# LampenSteuerung_PWM.net
KiCad netlist of a schematic drawn in EAGLE
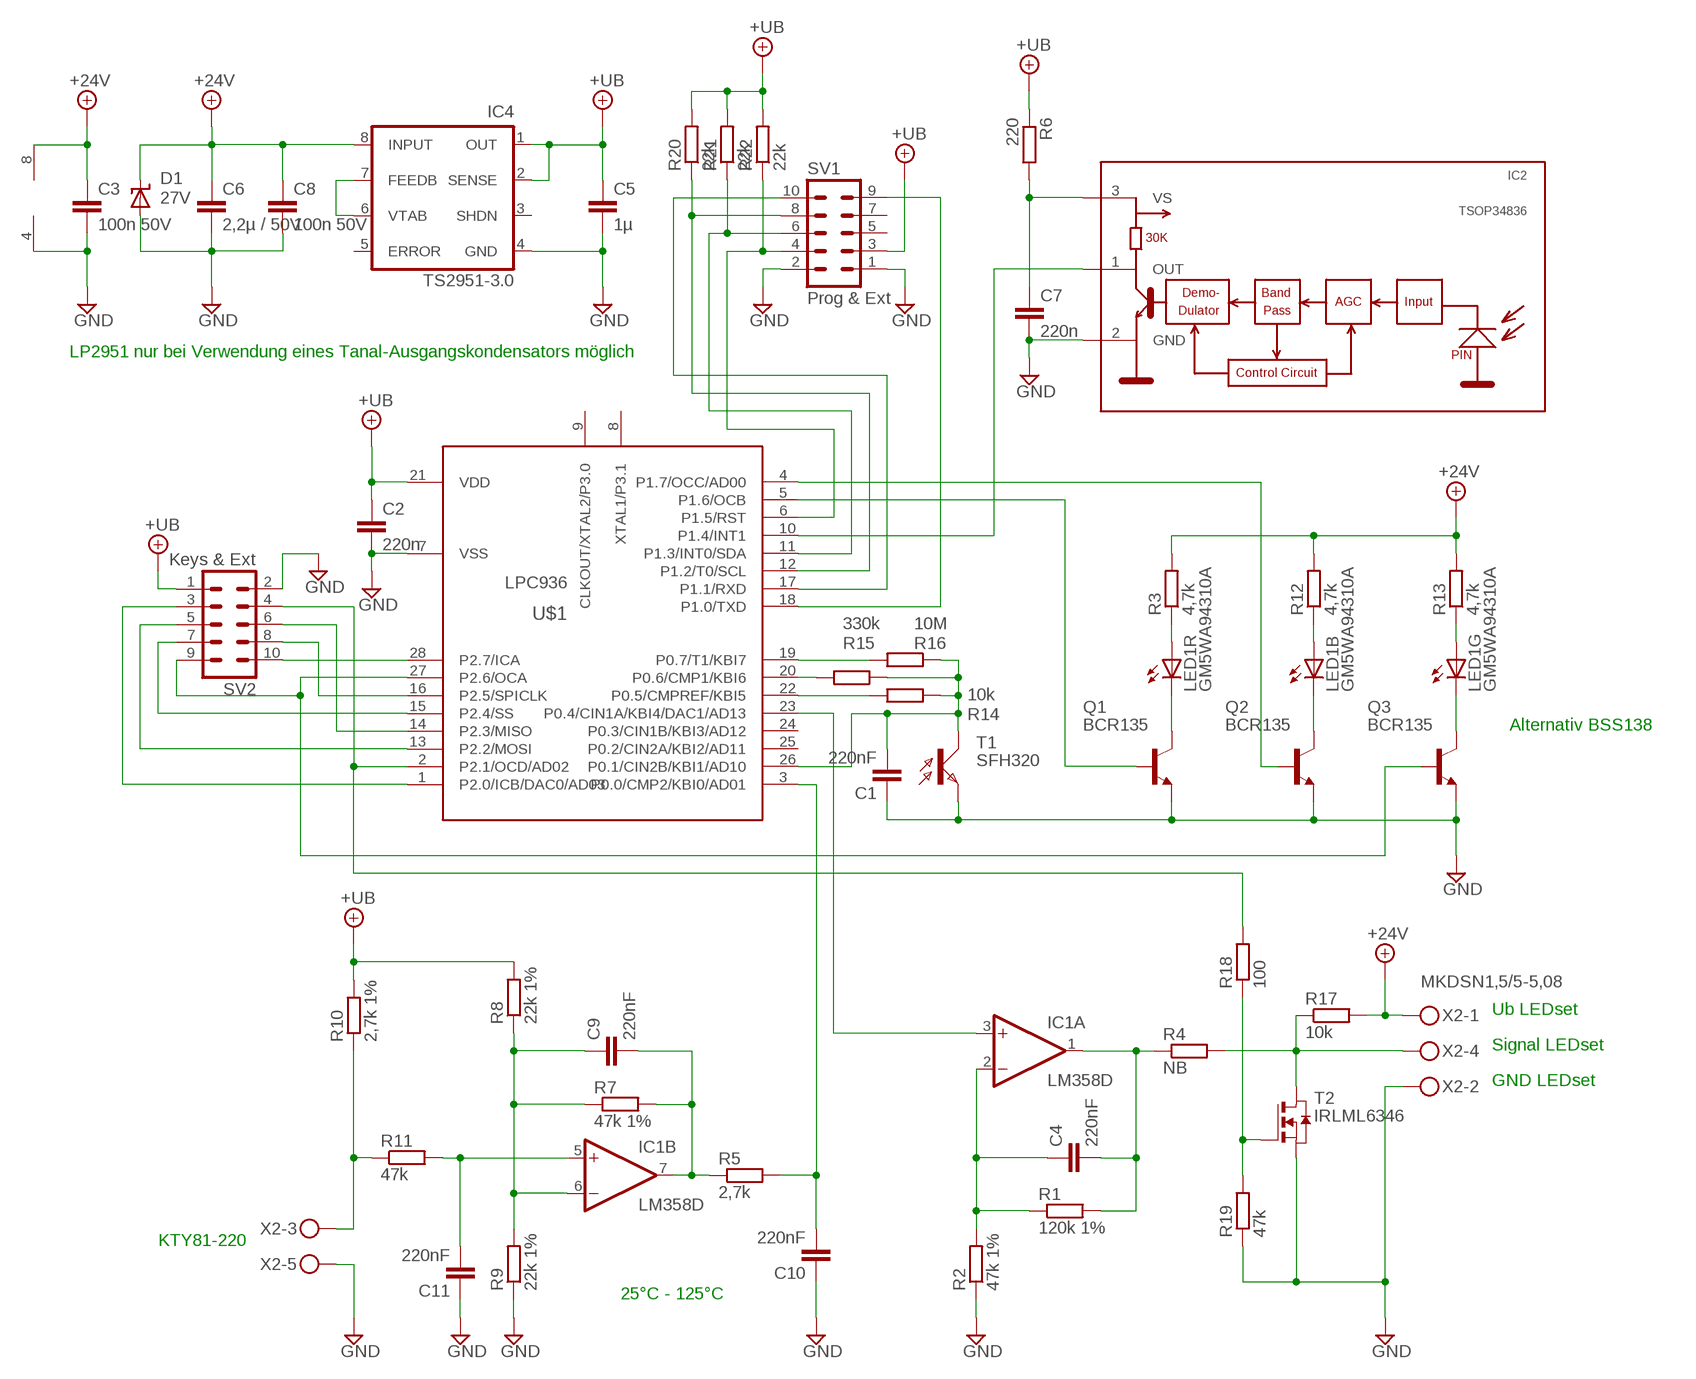
[diagram p0: schematic, sheet 1]

(export (version "E")
  (design (tool "Eeschema 10.0.6"))
  (components
    (comp (ref "C1")
      (value "220nF")
      (footprint "eagle-import:C0603")
      (libsource (lib "eagle-import") (part "C-EUC0603"))
    )
    (comp (ref "C2")
      (value "220n")
      (footprint "eagle-import:C0603")
      (libsource (lib "eagle-import") (part "C-EUC0603"))
    )
    (comp (ref "C3")
      (value "100n 50V")
      (footprint "eagle-import:C0603")
      (libsource (lib "eagle-import") (part "C-EUC0603"))
    )
    (comp (ref "C4")
      (value "220nF")
      (footprint "eagle-import:C0603")
      (libsource (lib "eagle-import") (part "C-EUC0603"))
    )
    (comp (ref "C5")
      (value "1µ")
      (footprint "eagle-import:C0805")
      (libsource (lib "eagle-import") (part "C-EUC0805"))
    )
    (comp (ref "C6")
      (value "2,2µ / 50V")
      (footprint "eagle-import:C1206")
      (libsource (lib "eagle-import") (part "C-EUC1206"))
    )
    (comp (ref "C7")
      (value "220n")
      (footprint "eagle-import:C0603")
      (libsource (lib "eagle-import") (part "C-EUC0603"))
    )
    (comp (ref "C8")
      (value "100n 50V")
      (footprint "eagle-import:C0603")
      (libsource (lib "eagle-import") (part "C-EUC0603"))
    )
    (comp (ref "C9")
      (value "220nF")
      (footprint "eagle-import:C0603")
      (libsource (lib "eagle-import") (part "C-EUC0603"))
    )
    (comp (ref "C10")
      (value "220nF")
      (footprint "eagle-import:C0603")
      (libsource (lib "eagle-import") (part "C-EUC0603"))
    )
    (comp (ref "C11")
      (value "220nF")
      (footprint "eagle-import:C0603")
      (libsource (lib "eagle-import") (part "C-EUC0603"))
    )
    (comp (ref "D1")
      (value "27V")
      (footprint "eagle-import:SMBJ")
      (libsource (lib "eagle-import") (part "SUPPRESSOR-SMBJ"))
    )
    (comp (ref "IC1")
      (value "LM358D")
      (footprint "eagle-import:SO08")
      (libsource (lib "eagle-import") (part "LM358D"))
    )
    (comp (ref "IC2")
      (value "TSOP34836")
      (footprint "eagle-import:TSOP348")
      (libsource (lib "eagle-import") (part "TSOP34836"))
    )
    (comp (ref "IC4")
      (value "TS2951-3.0")
      (footprint "eagle-import:SO-08")
      (libsource (lib "eagle-import") (part "LP2951?CM-3.0"))
    )
    (comp (ref "LED1")
      (value "GM5WA94310A")
      (footprint "eagle-import:GM5WA94310A")
      (libsource (lib "eagle-import") (part "GM5WA94310A"))
    )
    (comp (ref "Q1")
      (value "BCR135")
      (footprint "eagle-import:SOT23-BEC")
      (libsource (lib "eagle-import") (part "BCW60SMD"))
    )
    (comp (ref "Q2")
      (value "BCR135")
      (footprint "eagle-import:SOT23-BEC")
      (libsource (lib "eagle-import") (part "BCW60SMD"))
    )
    (comp (ref "Q3")
      (value "BCR135")
      (footprint "eagle-import:SOT23-BEC")
      (libsource (lib "eagle-import") (part "BCW60SMD"))
    )
    (comp (ref "R1")
      (value "120k 1%")
      (footprint "eagle-import:R0805")
      (libsource (lib "eagle-import") (part "R-EU_R0805"))
    )
    (comp (ref "R2")
      (value "47k 1%")
      (footprint "eagle-import:R0805")
      (libsource (lib "eagle-import") (part "R-EU_R0805"))
    )
    (comp (ref "R3")
      (value "4,7k")
      (footprint "eagle-import:R0805")
      (libsource (lib "eagle-import") (part "R-EU_R0805"))
    )
    (comp (ref "R4")
      (value "NB")
      (footprint "eagle-import:R0805")
      (libsource (lib "eagle-import") (part "R-EU_R0805"))
    )
    (comp (ref "R5")
      (value "2,7k")
      (footprint "eagle-import:R0805")
      (libsource (lib "eagle-import") (part "R-EU_R0805"))
    )
    (comp (ref "R6")
      (value "220")
      (footprint "eagle-import:R0805")
      (libsource (lib "eagle-import") (part "R-EU_R0805"))
    )
    (comp (ref "R7")
      (value "47k 1%")
      (footprint "eagle-import:R0805")
      (libsource (lib "eagle-import") (part "R-EU_R0805"))
    )
    (comp (ref "R8")
      (value "22k 1%")
      (footprint "eagle-import:R0805")
      (libsource (lib "eagle-import") (part "R-EU_R0805"))
    )
    (comp (ref "R9")
      (value "22k 1%")
      (footprint "eagle-import:R0805")
      (libsource (lib "eagle-import") (part "R-EU_R0805"))
    )
    (comp (ref "R10")
      (value "2,7k 1%")
      (footprint "eagle-import:R0805")
      (libsource (lib "eagle-import") (part "R-EU_R0805"))
    )
    (comp (ref "R11")
      (value "47k")
      (footprint "eagle-import:R0805")
      (libsource (lib "eagle-import") (part "R-EU_R0805"))
    )
    (comp (ref "R12")
      (value "4,7k")
      (footprint "eagle-import:R0805")
      (libsource (lib "eagle-import") (part "R-EU_R0805"))
    )
    (comp (ref "R13")
      (value "4,7k")
      (footprint "eagle-import:R0805")
      (libsource (lib "eagle-import") (part "R-EU_R0805"))
    )
    (comp (ref "R14")
      (value "10k")
      (footprint "eagle-import:R0805")
      (libsource (lib "eagle-import") (part "R-EU_R0805"))
    )
    (comp (ref "R15")
      (value "330k")
      (footprint "eagle-import:R0805")
      (libsource (lib "eagle-import") (part "R-EU_R0805"))
    )
    (comp (ref "R16")
      (value "10M")
      (footprint "eagle-import:R0805")
      (libsource (lib "eagle-import") (part "R-EU_R0805"))
    )
    (comp (ref "R17")
      (value "10k")
      (footprint "eagle-import:R0805")
      (libsource (lib "eagle-import") (part "R-EU_R0805"))
    )
    (comp (ref "R18")
      (value "100")
      (footprint "eagle-import:R0805")
      (libsource (lib "eagle-import") (part "R-EU_R0805"))
    )
    (comp (ref "R19")
      (value "47k")
      (footprint "eagle-import:R0805")
      (libsource (lib "eagle-import") (part "R-EU_R0805"))
    )
    (comp (ref "R20")
      (value "22k")
      (footprint "eagle-import:R0805")
      (libsource (lib "eagle-import") (part "R-EU_R0805"))
    )
    (comp (ref "R21")
      (value "22k")
      (footprint "eagle-import:R0805")
      (libsource (lib "eagle-import") (part "R-EU_R0805"))
    )
    (comp (ref "R22")
      (value "22k")
      (footprint "eagle-import:R0805")
      (libsource (lib "eagle-import") (part "R-EU_R0805"))
    )
    (comp (ref "SV1")
      (value "Prog & Ext")
      (footprint "eagle-import:MA05-2")
      (libsource (lib "eagle-import") (part "MA05-2"))
    )
    (comp (ref "SV2")
      (value "Keys & Ext")
      (footprint "eagle-import:MA05-2")
      (libsource (lib "eagle-import") (part "MA05-2"))
    )
    (comp (ref "T1")
      (value "SFH320")
      (footprint "eagle-import:PLCC2")
      (libsource (lib "eagle-import") (part "SFH320"))
    )
    (comp (ref "T2")
      (value "IRLML6346")
      (footprint "eagle-import:SOT-23")
      (libsource (lib "eagle-import") (part "NMOSSOT23"))
    )
    (comp (ref "U$1")
      (value "LPC936")
      (footprint "eagle-import:TSSOP28")
      (libsource (lib "eagle-import") (part "LPC936"))
    )
    (comp (ref "X2")
      (value "MKDSN1,5/5-5,08")
      (footprint "eagle-import:MKDSN1,5_5-5,08")
      (fields (field (name "MPN") "SMKDSN1,5/5-5,08"))
      (libsource (lib "eagle-import") (part "MKDSN1,5/5-5,08"))
    )
  )
  (nets
    (net (code "1") (name "+24V") (class "Default")
      (node (ref "C3") (pin "1") (pinfunction "1_1") (pintype "passive"))
      (node (ref "C6") (pin "1") (pinfunction "1_1") (pintype "passive"))
      (node (ref "C8") (pin "1") (pinfunction "1_1") (pintype "passive"))
      (node (ref "D1") (pin "C") (pinfunction "C_C") (pintype "passive"))
      (node (ref "IC1") (pin "8") (pinfunction "V+_8") (pintype "power_in"))
      (node (ref "IC4") (pin "8") (pinfunction "INPUT_8") (pintype "passive"))
      (node (ref "R12") (pin "2") (pinfunction "2_2") (pintype "passive"))
      (node (ref "R13") (pin "2") (pinfunction "2_2") (pintype "passive"))
      (node (ref "R17") (pin "2") (pinfunction "2_2") (pintype "passive"))
      (node (ref "R3") (pin "2") (pinfunction "2_2") (pintype "passive"))
      (node (ref "X2") (pin "1") (pinfunction "KL_1") (pintype "passive"))
    )
    (net (code "2") (name "+UB") (class "Default")
      (node (ref "C2") (pin "1") (pinfunction "1_1") (pintype "passive"))
      (node (ref "C5") (pin "1") (pinfunction "1_1") (pintype "passive"))
      (node (ref "IC4") (pin "1") (pinfunction "OUT_1") (pintype "output"))
      (node (ref "IC4") (pin "2") (pinfunction "SENSE_2") (pintype "input"))
      (node (ref "R10") (pin "2") (pinfunction "2_2") (pintype "passive"))
      (node (ref "R20") (pin "2") (pinfunction "2_2") (pintype "passive"))
      (node (ref "R21") (pin "2") (pinfunction "2_2") (pintype "passive"))
      (node (ref "R22") (pin "2") (pinfunction "2_2") (pintype "passive"))
      (node (ref "R6") (pin "1") (pinfunction "1_1") (pintype "passive"))
      (node (ref "R8") (pin "2") (pinfunction "2_2") (pintype "passive"))
      (node (ref "SV1") (pin "3") (pinfunction "3_3") (pintype "passive"))
      (node (ref "SV2") (pin "1") (pinfunction "1_1") (pintype "passive"))
      (node (ref "U$1") (pin "21") (pinfunction "VDD_21") (pintype "bidirectional"))
    )
    (net (code "3") (name "GND") (class "Default")
      (node (ref "C1") (pin "1") (pinfunction "1_1") (pintype "passive"))
      (node (ref "C10") (pin "1") (pinfunction "1_1") (pintype "passive"))
      (node (ref "C11") (pin "1") (pinfunction "1_1") (pintype "passive"))
      (node (ref "C2") (pin "2") (pinfunction "2_2") (pintype "passive"))
      (node (ref "C3") (pin "2") (pinfunction "2_2") (pintype "passive"))
      (node (ref "C5") (pin "2") (pinfunction "2_2") (pintype "passive"))
      (node (ref "C6") (pin "2") (pinfunction "2_2") (pintype "passive"))
      (node (ref "C7") (pin "2") (pinfunction "2_2") (pintype "passive"))
      (node (ref "C8") (pin "2") (pinfunction "2_2") (pintype "passive"))
      (node (ref "D1") (pin "A") (pinfunction "A_A") (pintype "passive"))
      (node (ref "IC1") (pin "4") (pinfunction "V-_4") (pintype "power_in"))
      (node (ref "IC2") (pin "2") (pinfunction "GND_2") (pintype "power_in"))
      (node (ref "IC4") (pin "4") (pinfunction "GND_4") (pintype "power_in"))
      (node (ref "Q1") (pin "E") (pinfunction "E_E") (pintype "passive"))
      (node (ref "Q2") (pin "E") (pinfunction "E_E") (pintype "passive"))
      (node (ref "Q3") (pin "E") (pinfunction "E_E") (pintype "passive"))
      (node (ref "R19") (pin "1") (pinfunction "1_1") (pintype "passive"))
      (node (ref "R2") (pin "1") (pinfunction "1_1") (pintype "passive"))
      (node (ref "R9") (pin "1") (pinfunction "1_1") (pintype "passive"))
      (node (ref "SV1") (pin "1") (pinfunction "1_1") (pintype "passive"))
      (node (ref "SV1") (pin "2") (pinfunction "2_2") (pintype "passive"))
      (node (ref "SV2") (pin "2") (pinfunction "2_2") (pintype "passive"))
      (node (ref "T1") (pin "C") (pinfunction "E_C") (pintype "passive"))
      (node (ref "T2") (pin "2") (pinfunction "S_2") (pintype "passive"))
      (node (ref "U$1") (pin "7") (pinfunction "VSS_7") (pintype "bidirectional"))
      (node (ref "X2") (pin "2") (pinfunction "KL_2") (pintype "passive"))
      (node (ref "X2") (pin "5") (pinfunction "KL_5") (pintype "passive"))
    )
    (net (code "4") (name "Net-(IC1A-+IN)") (class "Default")
      (node (ref "IC1") (pin "3") (pinfunction "+IN_3") (pintype "input"))
      (node (ref "U$1") (pin "23") (pinfunction "P0.4/CIN1A/KBI4/DAC1/AD13_23") (pintype "bidirectional"))
    )
    (net (code "5") (name "Net-(IC1A--IN)") (class "Default")
      (node (ref "C4") (pin "1") (pinfunction "1_1") (pintype "passive"))
      (node (ref "IC1") (pin "2") (pinfunction "-IN_2") (pintype "input"))
      (node (ref "R1") (pin "1") (pinfunction "1_1") (pintype "passive"))
      (node (ref "R2") (pin "2") (pinfunction "2_2") (pintype "passive"))
    )
    (net (code "6") (name "Net-(IC1A-OUT)") (class "Default")
      (node (ref "C4") (pin "2") (pinfunction "2_2") (pintype "passive"))
      (node (ref "IC1") (pin "1") (pinfunction "OUT_1") (pintype "output"))
      (node (ref "R1") (pin "2") (pinfunction "2_2") (pintype "passive"))
      (node (ref "R4") (pin "1") (pinfunction "1_1") (pintype "passive"))
    )
    (net (code "7") (name "Net-(IC1B-+IN)") (class "Default")
      (node (ref "C11") (pin "2") (pinfunction "2_2") (pintype "passive"))
      (node (ref "IC1") (pin "5") (pinfunction "+IN_5") (pintype "input"))
      (node (ref "R11") (pin "2") (pinfunction "2_2") (pintype "passive"))
    )
    (net (code "8") (name "Net-(IC1B--IN)") (class "Default")
      (node (ref "C9") (pin "1") (pinfunction "1_1") (pintype "passive"))
      (node (ref "IC1") (pin "6") (pinfunction "-IN_6") (pintype "input"))
      (node (ref "R7") (pin "1") (pinfunction "1_1") (pintype "passive"))
      (node (ref "R8") (pin "1") (pinfunction "1_1") (pintype "passive"))
      (node (ref "R9") (pin "2") (pinfunction "2_2") (pintype "passive"))
    )
    (net (code "9") (name "Net-(IC1B-OUT)") (class "Default")
      (node (ref "C9") (pin "2") (pinfunction "2_2") (pintype "passive"))
      (node (ref "IC1") (pin "7") (pinfunction "OUT_7") (pintype "output"))
      (node (ref "R5") (pin "1") (pinfunction "1_1") (pintype "passive"))
      (node (ref "R7") (pin "2") (pinfunction "2_2") (pintype "passive"))
    )
    (net (code "10") (name "Net-(IC2-OUT)") (class "Default")
      (node (ref "IC2") (pin "1") (pinfunction "OUT_1") (pintype "output"))
      (node (ref "U$1") (pin "10") (pinfunction "P1.4/INT1_10") (pintype "bidirectional"))
    )
    (net (code "11") (name "Net-(IC2-VS)") (class "Default")
      (node (ref "C7") (pin "1") (pinfunction "1_1") (pintype "passive"))
      (node (ref "IC2") (pin "3") (pinfunction "VS_3") (pintype "power_in"))
      (node (ref "R6") (pin "2") (pinfunction "2_2") (pintype "passive"))
    )
    (net (code "12") (name "Net-(IC4-FEEDB)") (class "Default")
      (node (ref "IC4") (pin "6") (pinfunction "VTAB_6") (pintype "input"))
      (node (ref "IC4") (pin "7") (pinfunction "FEEDB_7") (pintype "output"))
    )
    (net (code "13") (name "Net-(LED1A-A)") (class "Default")
      (node (ref "LED1") (pin "1") (pinfunction "A_1") (pintype "passive"))
      (node (ref "R12") (pin "1") (pinfunction "1_1") (pintype "passive"))
    )
    (net (code "14") (name "Net-(LED1A-C)") (class "Default")
      (node (ref "LED1") (pin "6") (pinfunction "C_6") (pintype "passive"))
      (node (ref "Q2") (pin "C") (pinfunction "C_C") (pintype "passive"))
    )
    (net (code "15") (name "Net-(LED1B-A)") (class "Default")
      (node (ref "LED1") (pin "3") (pinfunction "A_3") (pintype "passive"))
      (node (ref "R13") (pin "1") (pinfunction "1_1") (pintype "passive"))
    )
    (net (code "16") (name "Net-(LED1B-C)") (class "Default")
      (node (ref "LED1") (pin "4") (pinfunction "C_4") (pintype "passive"))
      (node (ref "Q3") (pin "C") (pinfunction "C_C") (pintype "passive"))
    )
    (net (code "17") (name "Net-(LED1C-A)") (class "Default")
      (node (ref "LED1") (pin "2") (pinfunction "A_2") (pintype "passive"))
      (node (ref "R3") (pin "1") (pinfunction "1_1") (pintype "passive"))
    )
    (net (code "18") (name "Net-(LED1C-C)") (class "Default")
      (node (ref "LED1") (pin "5") (pinfunction "C_5") (pintype "passive"))
      (node (ref "Q1") (pin "C") (pinfunction "C_C") (pintype "passive"))
    )
    (net (code "19") (name "Net-(T1-C)") (class "Default")
      (node (ref "C1") (pin "2") (pinfunction "2_2") (pintype "passive"))
      (node (ref "R14") (pin "1") (pinfunction "1_1") (pintype "passive"))
      (node (ref "R15") (pin "1") (pinfunction "1_1") (pintype "passive"))
      (node (ref "R16") (pin "1") (pinfunction "1_1") (pintype "passive"))
      (node (ref "T1") (pin "A") (pinfunction "C_A") (pintype "passive"))
      (node (ref "U$1") (pin "26") (pinfunction "P0.1/CIN2B/KBI1/AD10_26") (pintype "bidirectional"))
    )
    (net (code "20") (name "Net-(T2-D)") (class "Default")
      (node (ref "R17") (pin "1") (pinfunction "1_1") (pintype "passive"))
      (node (ref "R4") (pin "2") (pinfunction "2_2") (pintype "passive"))
      (node (ref "T2") (pin "1") (pinfunction "D_1") (pintype "passive"))
      (node (ref "X2") (pin "4") (pinfunction "KL_4") (pintype "passive"))
    )
    (net (code "21") (name "Net-(T2-G)") (class "Default")
      (node (ref "R18") (pin "1") (pinfunction "1_1") (pintype "passive"))
      (node (ref "R19") (pin "2") (pinfunction "2_2") (pintype "passive"))
      (node (ref "T2") (pin "3") (pinfunction "G_3") (pintype "passive"))
    )
    (net (code "22") (name "Net-(U$1-P0.0{slash}CMP2{slash}KBI0{slash}AD01)") (class "Default")
      (node (ref "C10") (pin "2") (pinfunction "2_2") (pintype "passive"))
      (node (ref "R5") (pin "2") (pinfunction "2_2") (pintype "passive"))
      (node (ref "U$1") (pin "3") (pinfunction "P0.0/CMP2/KBI0/AD01_3") (pintype "bidirectional"))
    )
    (net (code "23") (name "Net-(U$1-P0.5{slash}CMPREF{slash}KBI5)") (class "Default")
      (node (ref "R14") (pin "2") (pinfunction "2_2") (pintype "passive"))
      (node (ref "U$1") (pin "22") (pinfunction "P0.5/CMPREF/KBI5_22") (pintype "bidirectional"))
    )
    (net (code "24") (name "Net-(U$1-P0.6{slash}CMP1{slash}KBI6)") (class "Default")
      (node (ref "R15") (pin "2") (pinfunction "2_2") (pintype "passive"))
      (node (ref "U$1") (pin "20") (pinfunction "P0.6/CMP1/KBI6_20") (pintype "bidirectional"))
    )
    (net (code "25") (name "Net-(U$1-P0.7{slash}T1{slash}KBI7)") (class "Default")
      (node (ref "R16") (pin "2") (pinfunction "2_2") (pintype "passive"))
      (node (ref "U$1") (pin "19") (pinfunction "P0.7/T1/KBI7_19") (pintype "bidirectional"))
    )
    (net (code "26") (name "Net-(U$1-P1.0{slash}TXD)") (class "Default")
      (node (ref "SV1") (pin "9") (pinfunction "9_9") (pintype "passive"))
      (node (ref "U$1") (pin "18") (pinfunction "P1.0/TXD_18") (pintype "bidirectional"))
    )
    (net (code "27") (name "Net-(U$1-P1.1{slash}RXD)") (class "Default")
      (node (ref "SV1") (pin "10") (pinfunction "10_10") (pintype "passive"))
      (node (ref "U$1") (pin "17") (pinfunction "P1.1/RXD_17") (pintype "bidirectional"))
    )
    (net (code "28") (name "Net-(U$1-P1.2{slash}T0{slash}SCL)") (class "Default")
      (node (ref "R20") (pin "1") (pinfunction "1_1") (pintype "passive"))
      (node (ref "SV1") (pin "8") (pinfunction "8_8") (pintype "passive"))
      (node (ref "U$1") (pin "12") (pinfunction "P1.2/T0/SCL_12") (pintype "bidirectional"))
    )
    (net (code "29") (name "Net-(U$1-P1.3{slash}INT0{slash}SDA)") (class "Default")
      (node (ref "R21") (pin "1") (pinfunction "1_1") (pintype "passive"))
      (node (ref "SV1") (pin "6") (pinfunction "6_6") (pintype "passive"))
      (node (ref "U$1") (pin "11") (pinfunction "P1.3/INT0/SDA_11") (pintype "bidirectional"))
    )
    (net (code "30") (name "Net-(U$1-P1.5{slash}RST)") (class "Default")
      (node (ref "R22") (pin "1") (pinfunction "1_1") (pintype "passive"))
      (node (ref "SV1") (pin "4") (pinfunction "4_4") (pintype "passive"))
      (node (ref "U$1") (pin "6") (pinfunction "P1.5/RST_6") (pintype "bidirectional"))
    )
    (net (code "31") (name "Net-(U$1-P1.6{slash}OCB)") (class "Default")
      (node (ref "Q1") (pin "B") (pinfunction "B_B") (pintype "passive"))
      (node (ref "U$1") (pin "5") (pinfunction "P1.6/OCB_5") (pintype "bidirectional"))
    )
    (net (code "32") (name "Net-(U$1-P1.7{slash}OCC{slash}AD00)") (class "Default")
      (node (ref "Q2") (pin "B") (pinfunction "B_B") (pintype "passive"))
      (node (ref "U$1") (pin "4") (pinfunction "P1.7/OCC/AD00_4") (pintype "bidirectional"))
    )
    (net (code "33") (name "Net-(U$1-P2.0{slash}ICB{slash}DAC0{slash}AD03)") (class "Default")
      (node (ref "SV2") (pin "3") (pinfunction "3_3") (pintype "passive"))
      (node (ref "U$1") (pin "1") (pinfunction "P2.0/ICB/DAC0/AD03_1") (pintype "bidirectional"))
    )
    (net (code "34") (name "Net-(U$1-P2.1{slash}OCD{slash}AD02)") (class "Default")
      (node (ref "R18") (pin "2") (pinfunction "2_2") (pintype "passive"))
      (node (ref "SV2") (pin "4") (pinfunction "4_4") (pintype "passive"))
      (node (ref "U$1") (pin "2") (pinfunction "P2.1/OCD/AD02_2") (pintype "bidirectional"))
    )
    (net (code "35") (name "Net-(U$1-P2.2{slash}MOSI)") (class "Default")
      (node (ref "SV2") (pin "5") (pinfunction "5_5") (pintype "passive"))
      (node (ref "U$1") (pin "13") (pinfunction "P2.2/MOSI_13") (pintype "bidirectional"))
    )
    (net (code "36") (name "Net-(U$1-P2.3{slash}MISO)") (class "Default")
      (node (ref "SV2") (pin "6") (pinfunction "6_6") (pintype "passive"))
      (node (ref "U$1") (pin "14") (pinfunction "P2.3/MISO_14") (pintype "bidirectional"))
    )
    (net (code "37") (name "Net-(U$1-P2.4{slash}SS)") (class "Default")
      (node (ref "SV2") (pin "7") (pinfunction "7_7") (pintype "passive"))
      (node (ref "U$1") (pin "15") (pinfunction "P2.4/SS_15") (pintype "bidirectional"))
    )
    (net (code "38") (name "Net-(U$1-P2.5{slash}SPICLK)") (class "Default")
      (node (ref "SV2") (pin "8") (pinfunction "8_8") (pintype "passive"))
      (node (ref "U$1") (pin "16") (pinfunction "P2.5/SPICLK_16") (pintype "bidirectional"))
    )
    (net (code "39") (name "Net-(U$1-P2.6{slash}OCA)") (class "Default")
      (node (ref "Q3") (pin "B") (pinfunction "B_B") (pintype "passive"))
      (node (ref "SV2") (pin "9") (pinfunction "9_9") (pintype "passive"))
      (node (ref "U$1") (pin "27") (pinfunction "P2.6/OCA_27") (pintype "bidirectional"))
    )
    (net (code "40") (name "Net-(U$1-P2.7{slash}ICA)") (class "Default")
      (node (ref "SV2") (pin "10") (pinfunction "10_10") (pintype "passive"))
      (node (ref "U$1") (pin "28") (pinfunction "P2.7/ICA_28") (pintype "bidirectional"))
    )
    (net (code "41") (name "Net-(X2C-KL)") (class "Default")
      (node (ref "R10") (pin "1") (pinfunction "1_1") (pintype "passive"))
      (node (ref "R11") (pin "1") (pinfunction "1_1") (pintype "passive"))
      (node (ref "X2") (pin "3") (pinfunction "KL_3") (pintype "passive"))
    )
    (net (code "42") (name "unconnected-(IC4-ERROR-Pad5)") (class "Default")
      (node (ref "IC4") (pin "5") (pinfunction "ERROR_5") (pintype "output"))
    )
    (net (code "43") (name "unconnected-(IC4-SHDN-Pad3)") (class "Default")
      (node (ref "IC4") (pin "3") (pinfunction "SHDN_3") (pintype "input"))
    )
    (net (code "44") (name "unconnected-(SV1-Pad5)") (class "Default")
      (node (ref "SV1") (pin "5") (pinfunction "5_5") (pintype "passive"))
    )
    (net (code "45") (name "unconnected-(SV1-Pad7)") (class "Default")
      (node (ref "SV1") (pin "7") (pinfunction "7_7") (pintype "passive"))
    )
    (net (code "46") (name "unconnected-(U$1-CLKOUT{slash}XTAL2{slash}P3.0-Pad9)") (class "Default")
      (node (ref "U$1") (pin "9") (pinfunction "CLKOUT/XTAL2/P3.0_9") (pintype "bidirectional"))
    )
    (net (code "47") (name "unconnected-(U$1-P0.2{slash}CIN2A{slash}KBI2{slash}AD11-Pad25)") (class "Default")
      (node (ref "U$1") (pin "25") (pinfunction "P0.2/CIN2A/KBI2/AD11_25") (pintype "bidirectional"))
    )
    (net (code "48") (name "unconnected-(U$1-P0.3{slash}CIN1B{slash}KBI3{slash}AD12-Pad24)") (class "Default")
      (node (ref "U$1") (pin "24") (pinfunction "P0.3/CIN1B/KBI3/AD12_24") (pintype "bidirectional"))
    )
    (net (code "49") (name "unconnected-(U$1-XTAL1{slash}P3.1-Pad8)") (class "Default")
      (node (ref "U$1") (pin "8") (pinfunction "XTAL1/P3.1_8") (pintype "bidirectional"))
    )
  )
)
